# Amplifier_Module_A.net
KiCad netlist of a schematic drawn in EasyEDA Pro
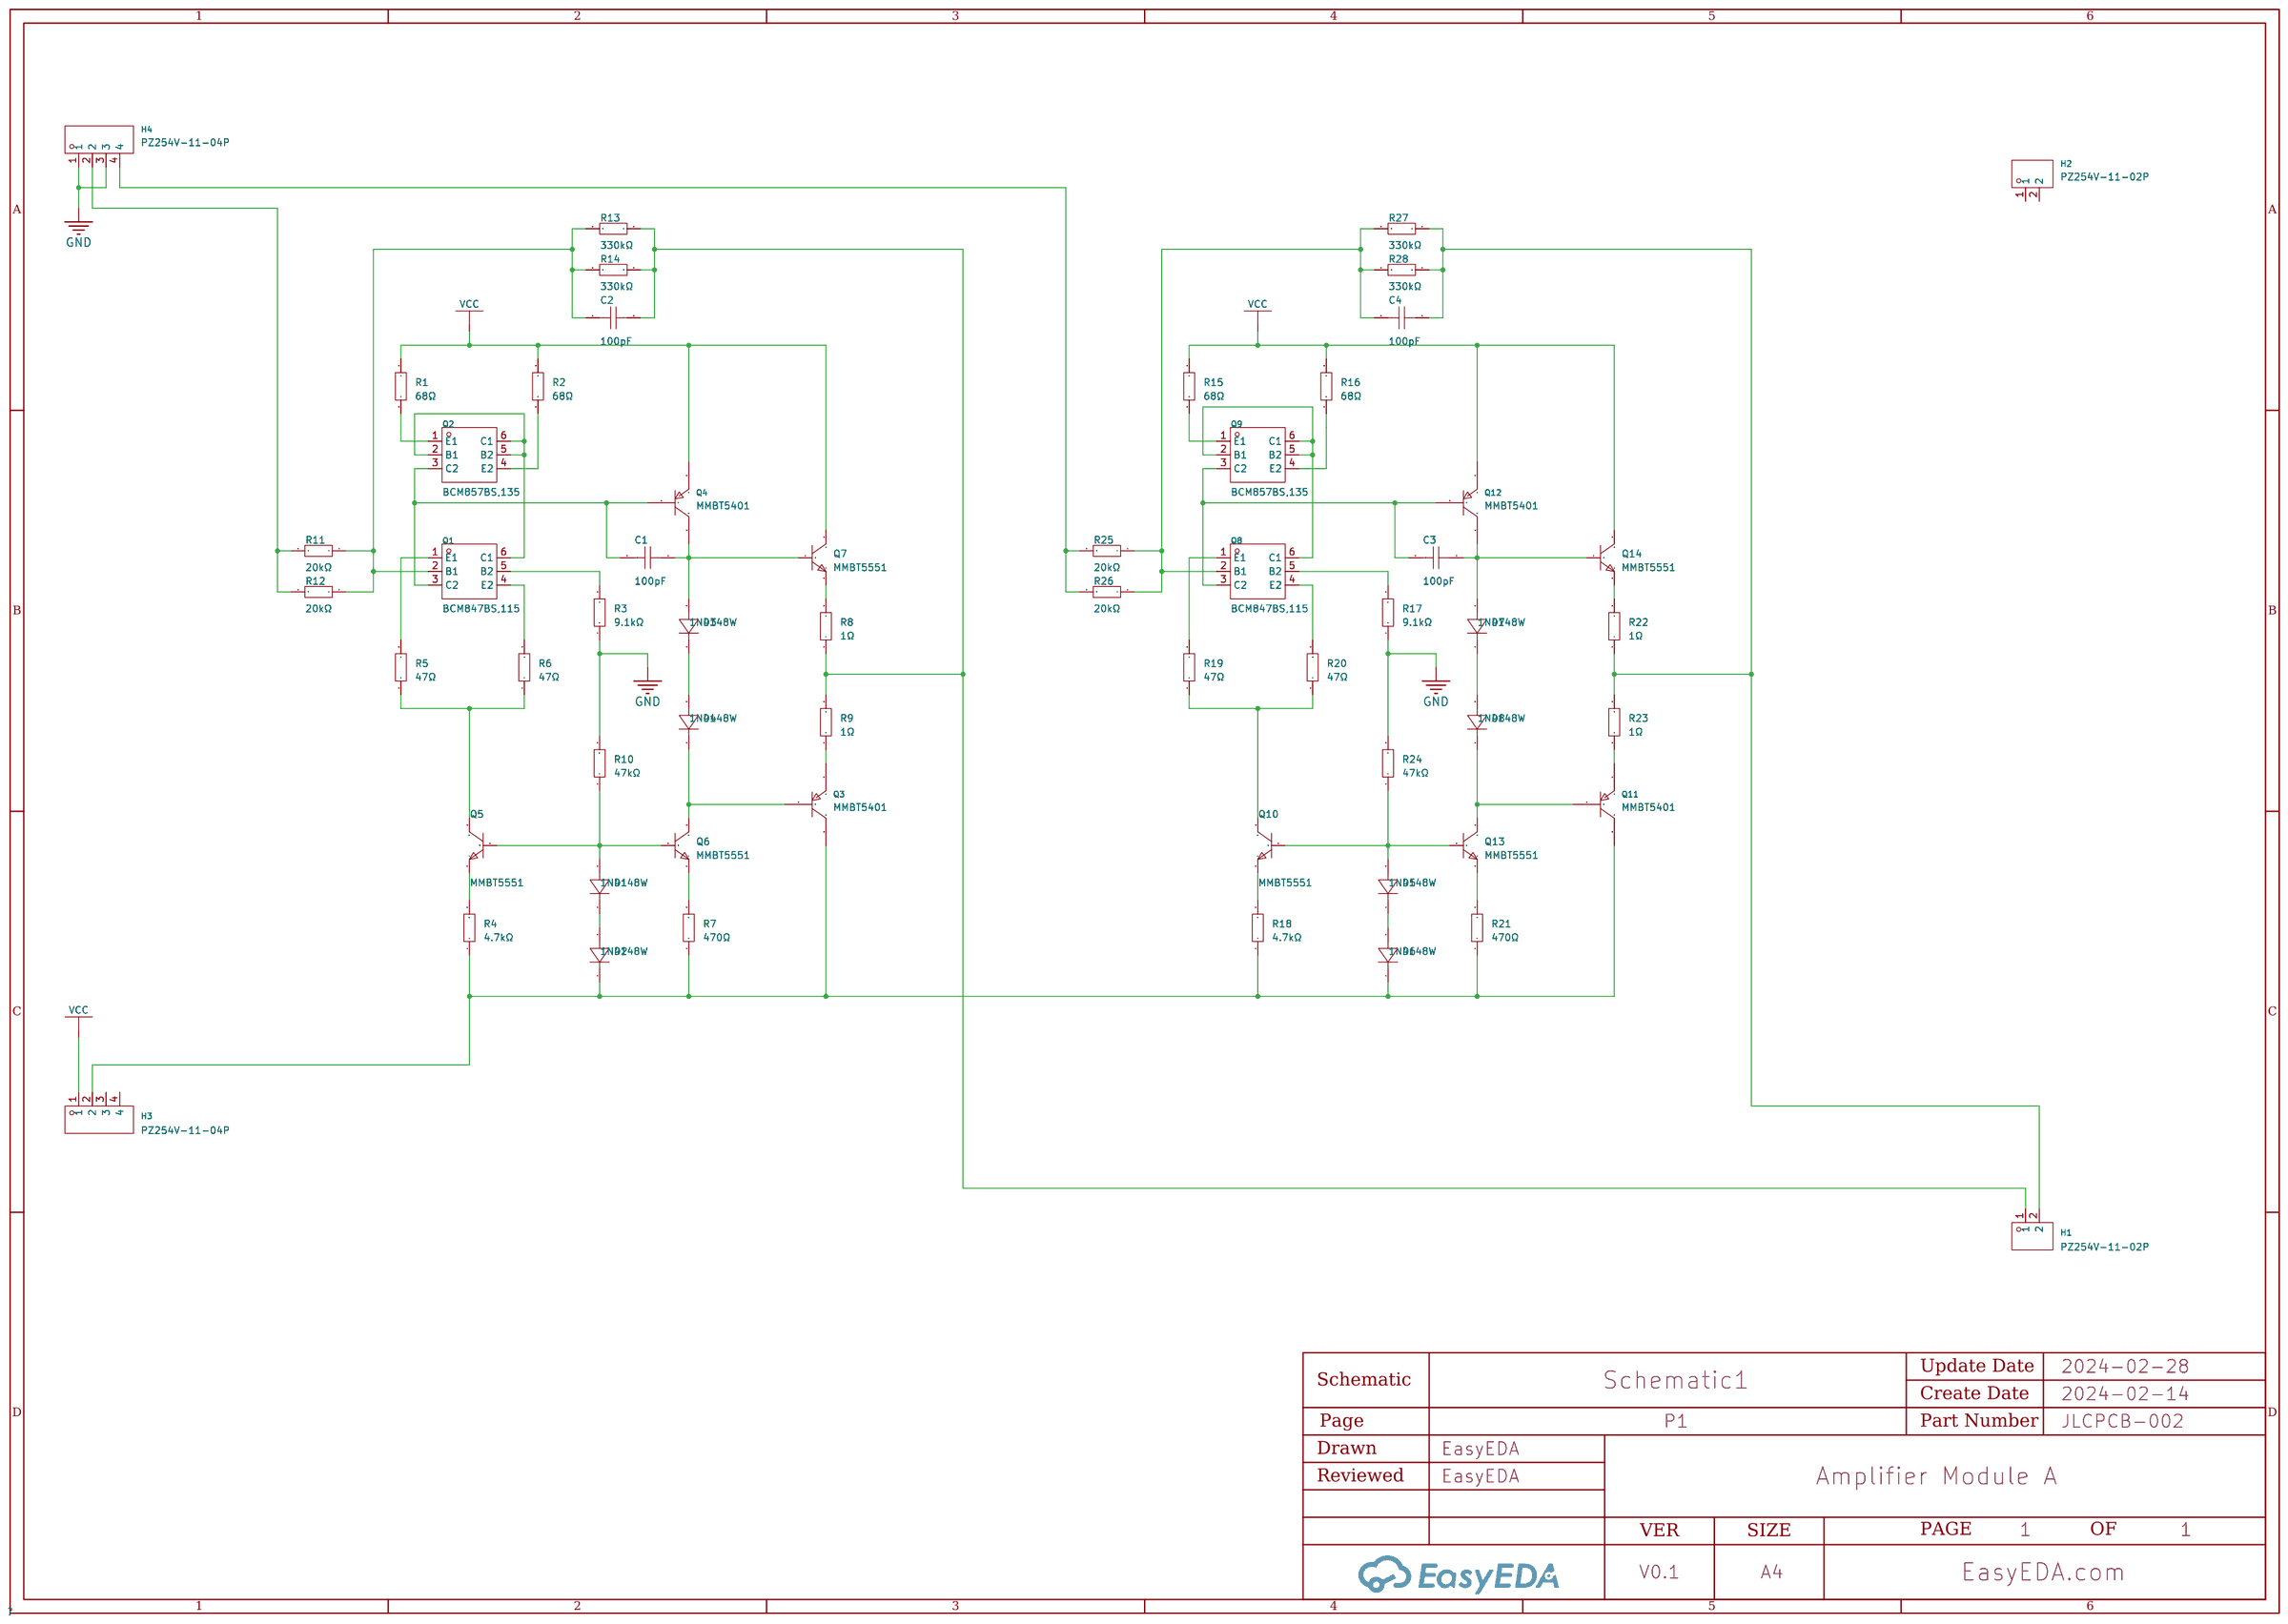
[diagram p0: schematic sheet]

(export (version "E")
  (design (tool "Eeschema 10.0.6"))
  (components
    (comp (ref "C1")
      (value "100pF")
      (footprint "easyedapro:C0603")
      (fields (field (name "Manufacturer Part") "0603CG101J101NT") (field (name "Manufacturer") "FH(风华)"))
      (libsource (lib "easyedapro") (part "CAP"))
    )
    (comp (ref "C2")
      (value "100pF")
      (footprint "easyedapro:C0603")
      (fields (field (name "Manufacturer Part") "0603CG101J101NT") (field (name "Manufacturer") "FH(风华)"))
      (libsource (lib "easyedapro") (part "CAP"))
    )
    (comp (ref "C3")
      (value "100pF")
      (footprint "easyedapro:C0603")
      (fields (field (name "Manufacturer Part") "0603CG101J101NT") (field (name "Manufacturer") "FH(风华)"))
      (libsource (lib "easyedapro") (part "CAP"))
    )
    (comp (ref "C4")
      (value "100pF")
      (footprint "easyedapro:C0603")
      (fields (field (name "Manufacturer Part") "0603CG101J101NT") (field (name "Manufacturer") "FH(风华)"))
      (libsource (lib "easyedapro") (part "CAP"))
    )
    (comp (ref "D1")
      (value "1N4148W")
      (footprint "easyedapro:DO-41_BD2.4-L4.7-P8.70-D0.9-RD")
      (fields (field (name "Manufacturer") "ST(先科)"))
      (libsource (lib "easyedapro") (part "D_1N4007"))
    )
    (comp (ref "D2")
      (value "1N4148W")
      (footprint "easyedapro:DO-41_BD2.4-L4.7-P8.70-D0.9-RD")
      (fields (field (name "Manufacturer") "ST(先科)"))
      (libsource (lib "easyedapro") (part "D_1N4007"))
    )
    (comp (ref "D3")
      (value "1N4148W")
      (footprint "easyedapro:DO-41_BD2.4-L4.7-P8.70-D0.9-RD")
      (fields (field (name "Manufacturer") "ST(先科)"))
      (libsource (lib "easyedapro") (part "D_1N4007"))
    )
    (comp (ref "D4")
      (value "1N4148W")
      (footprint "easyedapro:DO-41_BD2.4-L4.7-P8.70-D0.9-RD")
      (fields (field (name "Manufacturer") "ST(先科)"))
      (libsource (lib "easyedapro") (part "D_1N4007"))
    )
    (comp (ref "D5")
      (value "1N4148W")
      (footprint "easyedapro:DO-41_BD2.4-L4.7-P8.70-D0.9-RD")
      (fields (field (name "Manufacturer") "ST(先科)"))
      (libsource (lib "easyedapro") (part "D_1N4007"))
    )
    (comp (ref "D6")
      (value "1N4148W")
      (footprint "easyedapro:DO-41_BD2.4-L4.7-P8.70-D0.9-RD")
      (fields (field (name "Manufacturer") "ST(先科)"))
      (libsource (lib "easyedapro") (part "D_1N4007"))
    )
    (comp (ref "D7")
      (value "1N4148W")
      (footprint "easyedapro:DO-41_BD2.4-L4.7-P8.70-D0.9-RD")
      (fields (field (name "Manufacturer") "ST(先科)"))
      (libsource (lib "easyedapro") (part "D_1N4007"))
    )
    (comp (ref "D8")
      (value "1N4148W")
      (footprint "easyedapro:DO-41_BD2.4-L4.7-P8.70-D0.9-RD")
      (fields (field (name "Manufacturer") "ST(先科)"))
      (libsource (lib "easyedapro") (part "D_1N4007"))
    )
    (comp (ref "H1")
      (value "PZ254V-11-02P")
      (footprint "easyedapro:HDR-TH_2P-P2.54-V-M")
      (fields (field (name "Manufacturer") "XFCN(兴飞)"))
      (libsource (lib "easyedapro") (part "PZ254V-11-02P"))
    )
    (comp (ref "H2")
      (value "PZ254V-11-02P")
      (footprint "easyedapro:HDR-TH_2P-P2.54-V-M")
      (fields (field (name "Manufacturer") "XFCN(兴飞)"))
      (libsource (lib "easyedapro") (part "PZ254V-11-02P"))
    )
    (comp (ref "H3")
      (value "PZ254V-11-04P")
      (footprint "easyedapro:HDR-TH_4P-P2.54-V-M")
      (fields (field (name "Manufacturer") "XFCN(兴飞)"))
      (libsource (lib "easyedapro") (part "PZ254V-11-04P_C2691448"))
    )
    (comp (ref "H4")
      (value "PZ254V-11-04P")
      (footprint "easyedapro:HDR-TH_4P-P2.54-V-M")
      (fields (field (name "Manufacturer") "XFCN(兴飞)"))
      (libsource (lib "easyedapro") (part "PZ254V-11-04P_C2691448"))
    )
    (comp (ref "Q1")
      (value "BCM847BS,115")
      (footprint "easyedapro:SOT-363_L2.0-W1.3-P0.65-LS2.1-TL")
      (fields (field (name "Manufacturer") "Nexperia(安世)"))
      (libsource (lib "easyedapro") (part "BCM847BS,115"))
    )
    (comp (ref "Q2")
      (value "BCM857BS,135")
      (footprint "easyedapro:SOT-363_L2.0-W1.3-P0.65-LS2.1-BL")
      (fields (field (name "Manufacturer") "Nexperia(安世)"))
      (libsource (lib "easyedapro") (part "BCM857BS,135"))
    )
    (comp (ref "Q3")
      (value "MMBT5401")
      (footprint "easyedapro:SOT-23-3_L2.9-W1.6-P1.90-LS2.8-BR")
      (fields (field (name "Manufacturer") "CJ(江苏长电/长晶)"))
      (libsource (lib "easyedapro") (part "MMBT5401_C83941"))
    )
    (comp (ref "Q4")
      (value "MMBT5401")
      (footprint "easyedapro:SOT-23-3_L2.9-W1.6-P1.90-LS2.8-BR")
      (fields (field (name "Manufacturer") "CJ(江苏长电/长晶)"))
      (libsource (lib "easyedapro") (part "MMBT5401_C83941"))
    )
    (comp (ref "Q5")
      (value "MMBT5551")
      (footprint "easyedapro:SOT-23-3_L2.9-W1.6-P1.90-LS2.8-BR")
      (fields (field (name "Manufacturer") "CJ(江苏长电/长晶)"))
      (libsource (lib "easyedapro") (part "MMBT5551_C7603181"))
    )
    (comp (ref "Q6")
      (value "MMBT5551")
      (footprint "easyedapro:SOT-23-3_L2.9-W1.6-P1.90-LS2.8-BR")
      (fields (field (name "Manufacturer") "CJ(江苏长电/长晶)"))
      (libsource (lib "easyedapro") (part "MMBT5551_C7603181"))
    )
    (comp (ref "Q7")
      (value "MMBT5551")
      (footprint "easyedapro:SOT-23-3_L2.9-W1.6-P1.90-LS2.8-BR")
      (fields (field (name "Manufacturer") "CJ(江苏长电/长晶)"))
      (libsource (lib "easyedapro") (part "MMBT5551_C7603181"))
    )
    (comp (ref "Q8")
      (value "BCM847BS,115")
      (footprint "easyedapro:SOT-363_L2.0-W1.3-P0.65-LS2.1-TL")
      (fields (field (name "Manufacturer") "Nexperia(安世)"))
      (libsource (lib "easyedapro") (part "BCM847BS,115"))
    )
    (comp (ref "Q9")
      (value "BCM857BS,135")
      (footprint "easyedapro:SOT-363_L2.0-W1.3-P0.65-LS2.1-BL")
      (fields (field (name "Manufacturer") "Nexperia(安世)"))
      (libsource (lib "easyedapro") (part "BCM857BS,135"))
    )
    (comp (ref "Q10")
      (value "MMBT5551")
      (footprint "easyedapro:SOT-23-3_L2.9-W1.6-P1.90-LS2.8-BR")
      (fields (field (name "Manufacturer") "CJ(江苏长电/长晶)"))
      (libsource (lib "easyedapro") (part "MMBT5551_C7603181"))
    )
    (comp (ref "Q11")
      (value "MMBT5401")
      (footprint "easyedapro:SOT-23-3_L2.9-W1.6-P1.90-LS2.8-BR")
      (fields (field (name "Manufacturer") "CJ(江苏长电/长晶)"))
      (libsource (lib "easyedapro") (part "MMBT5401_C83941"))
    )
    (comp (ref "Q12")
      (value "MMBT5401")
      (footprint "easyedapro:SOT-23-3_L2.9-W1.6-P1.90-LS2.8-BR")
      (fields (field (name "Manufacturer") "CJ(江苏长电/长晶)"))
      (libsource (lib "easyedapro") (part "MMBT5401_C83941"))
    )
    (comp (ref "Q13")
      (value "MMBT5551")
      (footprint "easyedapro:SOT-23-3_L2.9-W1.6-P1.90-LS2.8-BR")
      (fields (field (name "Manufacturer") "CJ(江苏长电/长晶)"))
      (libsource (lib "easyedapro") (part "MMBT5551_C7603181"))
    )
    (comp (ref "Q14")
      (value "MMBT5551")
      (footprint "easyedapro:SOT-23-3_L2.9-W1.6-P1.90-LS2.8-BR")
      (fields (field (name "Manufacturer") "CJ(江苏长电/长晶)"))
      (libsource (lib "easyedapro") (part "MMBT5551_C7603181"))
    )
    (comp (ref "R1")
      (value "68Ω")
      (footprint "easyedapro:R0603")
      (fields
        (field (name "Manufacturer Part") "0603WAF680JT5E")
        (field (name "Manufacturer") "UNI-ROYAL(厚声)")
      )
      (libsource (lib "easyedapro") (part "Res"))
    )
    (comp (ref "R2")
      (value "68Ω")
      (footprint "easyedapro:R0603")
      (fields
        (field (name "Manufacturer Part") "0603WAF680JT5E")
        (field (name "Manufacturer") "UNI-ROYAL(厚声)")
      )
      (libsource (lib "easyedapro") (part "Res"))
    )
    (comp (ref "R3")
      (value "9.1kΩ")
      (footprint "easyedapro:R0603")
      (fields
        (field (name "Manufacturer Part") "0603WAF9101T5E")
        (field (name "Manufacturer") "UNI-ROYAL(厚声)")
      )
      (libsource (lib "easyedapro") (part "Res"))
    )
    (comp (ref "R4")
      (value "4.7kΩ")
      (footprint "easyedapro:R0603")
      (fields
        (field (name "Manufacturer Part") "0603WAF4701T5E")
        (field (name "Manufacturer") "UNI-ROYAL(厚声)")
      )
      (libsource (lib "easyedapro") (part "Res"))
    )
    (comp (ref "R5")
      (value "47Ω")
      (footprint "easyedapro:R0603")
      (fields
        (field (name "Manufacturer Part") "0603WAF470JT5E")
        (field (name "Manufacturer") "UNI-ROYAL(厚声)")
      )
      (libsource (lib "easyedapro") (part "Res"))
    )
    (comp (ref "R6")
      (value "47Ω")
      (footprint "easyedapro:R0603")
      (fields
        (field (name "Manufacturer Part") "0603WAF470JT5E")
        (field (name "Manufacturer") "UNI-ROYAL(厚声)")
      )
      (libsource (lib "easyedapro") (part "Res"))
    )
    (comp (ref "R7")
      (value "470Ω")
      (footprint "easyedapro:R0603")
      (fields
        (field (name "Manufacturer Part") "0603WAF4700T5E")
        (field (name "Manufacturer") "UNI-ROYAL(厚声)")
      )
      (libsource (lib "easyedapro") (part "Res"))
    )
    (comp (ref "R8")
      (value "1Ω")
      (footprint "easyedapro:R0603")
      (fields
        (field (name "Manufacturer Part") "0603WAF100KT5E")
        (field (name "Manufacturer") "UNI-ROYAL(厚声)")
      )
      (libsource (lib "easyedapro") (part "Res"))
    )
    (comp (ref "R9")
      (value "1Ω")
      (footprint "easyedapro:R0603")
      (fields
        (field (name "Manufacturer Part") "0603WAF100KT5E")
        (field (name "Manufacturer") "UNI-ROYAL(厚声)")
      )
      (libsource (lib "easyedapro") (part "Res"))
    )
    (comp (ref "R10")
      (value "47kΩ")
      (footprint "easyedapro:R0603")
      (fields
        (field (name "Manufacturer Part") "0603WAF4702T5E")
        (field (name "Manufacturer") "UNI-ROYAL(厚声)")
      )
      (libsource (lib "easyedapro") (part "Res"))
    )
    (comp (ref "R11")
      (value "20kΩ")
      (footprint "easyedapro:R0603")
      (fields
        (field (name "Manufacturer Part") "0603WAF2002T5E")
        (field (name "Manufacturer") "UNI-ROYAL(厚声)")
      )
      (libsource (lib "easyedapro") (part "Res"))
    )
    (comp (ref "R12")
      (value "20kΩ")
      (footprint "easyedapro:R0603")
      (fields
        (field (name "Manufacturer Part") "0603WAF2002T5E")
        (field (name "Manufacturer") "UNI-ROYAL(厚声)")
      )
      (libsource (lib "easyedapro") (part "Res"))
    )
    (comp (ref "R13")
      (value "330kΩ")
      (footprint "easyedapro:R0603")
      (fields
        (field (name "Manufacturer Part") "0603WAF3303T5E")
        (field (name "Manufacturer") "UNI-ROYAL(厚声)")
      )
      (libsource (lib "easyedapro") (part "Res"))
    )
    (comp (ref "R14")
      (value "330kΩ")
      (footprint "easyedapro:R0603")
      (fields
        (field (name "Manufacturer Part") "0603WAF3303T5E")
        (field (name "Manufacturer") "UNI-ROYAL(厚声)")
      )
      (libsource (lib "easyedapro") (part "Res"))
    )
    (comp (ref "R15")
      (value "68Ω")
      (footprint "easyedapro:R0603")
      (fields
        (field (name "Manufacturer Part") "0603WAF680JT5E")
        (field (name "Manufacturer") "UNI-ROYAL(厚声)")
      )
      (libsource (lib "easyedapro") (part "Res"))
    )
    (comp (ref "R16")
      (value "68Ω")
      (footprint "easyedapro:R0603")
      (fields
        (field (name "Manufacturer Part") "0603WAF680JT5E")
        (field (name "Manufacturer") "UNI-ROYAL(厚声)")
      )
      (libsource (lib "easyedapro") (part "Res"))
    )
    (comp (ref "R17")
      (value "9.1kΩ")
      (footprint "easyedapro:R0603")
      (fields
        (field (name "Manufacturer Part") "0603WAF9101T5E")
        (field (name "Manufacturer") "UNI-ROYAL(厚声)")
      )
      (libsource (lib "easyedapro") (part "Res"))
    )
    (comp (ref "R18")
      (value "4.7kΩ")
      (footprint "easyedapro:R0603")
      (fields
        (field (name "Manufacturer Part") "0603WAF4701T5E")
        (field (name "Manufacturer") "UNI-ROYAL(厚声)")
      )
      (libsource (lib "easyedapro") (part "Res"))
    )
    (comp (ref "R19")
      (value "47Ω")
      (footprint "easyedapro:R0603")
      (fields
        (field (name "Manufacturer Part") "0603WAF470JT5E")
        (field (name "Manufacturer") "UNI-ROYAL(厚声)")
      )
      (libsource (lib "easyedapro") (part "Res"))
    )
    (comp (ref "R20")
      (value "47Ω")
      (footprint "easyedapro:R0603")
      (fields
        (field (name "Manufacturer Part") "0603WAF470JT5E")
        (field (name "Manufacturer") "UNI-ROYAL(厚声)")
      )
      (libsource (lib "easyedapro") (part "Res"))
    )
    (comp (ref "R21")
      (value "470Ω")
      (footprint "easyedapro:R0603")
      (fields
        (field (name "Manufacturer Part") "0603WAF4700T5E")
        (field (name "Manufacturer") "UNI-ROYAL(厚声)")
      )
      (libsource (lib "easyedapro") (part "Res"))
    )
    (comp (ref "R22")
      (value "1Ω")
      (footprint "easyedapro:R0603")
      (fields
        (field (name "Manufacturer Part") "0603WAF100KT5E")
        (field (name "Manufacturer") "UNI-ROYAL(厚声)")
      )
      (libsource (lib "easyedapro") (part "Res"))
    )
    (comp (ref "R23")
      (value "1Ω")
      (footprint "easyedapro:R0603")
      (fields
        (field (name "Manufacturer Part") "0603WAF100KT5E")
        (field (name "Manufacturer") "UNI-ROYAL(厚声)")
      )
      (libsource (lib "easyedapro") (part "Res"))
    )
    (comp (ref "R24")
      (value "47kΩ")
      (footprint "easyedapro:R0603")
      (fields
        (field (name "Manufacturer Part") "0603WAF4702T5E")
        (field (name "Manufacturer") "UNI-ROYAL(厚声)")
      )
      (libsource (lib "easyedapro") (part "Res"))
    )
    (comp (ref "R25")
      (value "20kΩ")
      (footprint "easyedapro:R0603")
      (fields
        (field (name "Manufacturer Part") "0603WAF2002T5E")
        (field (name "Manufacturer") "UNI-ROYAL(厚声)")
      )
      (libsource (lib "easyedapro") (part "Res"))
    )
    (comp (ref "R26")
      (value "20kΩ")
      (footprint "easyedapro:R0603")
      (fields
        (field (name "Manufacturer Part") "0603WAF2002T5E")
        (field (name "Manufacturer") "UNI-ROYAL(厚声)")
      )
      (libsource (lib "easyedapro") (part "Res"))
    )
    (comp (ref "R27")
      (value "330kΩ")
      (footprint "easyedapro:R0603")
      (fields
        (field (name "Manufacturer Part") "0603WAF3303T5E")
        (field (name "Manufacturer") "UNI-ROYAL(厚声)")
      )
      (libsource (lib "easyedapro") (part "Res"))
    )
    (comp (ref "R28")
      (value "330kΩ")
      (footprint "easyedapro:R0603")
      (fields
        (field (name "Manufacturer Part") "0603WAF3303T5E")
        (field (name "Manufacturer") "UNI-ROYAL(厚声)")
      )
      (libsource (lib "easyedapro") (part "Res"))
    )
  )
  (nets
    (net (code "1") (name "GND") (class "Default")
      (node (ref "H4") (pin "1") (pinfunction "1_1") (pintype "input"))
      (node (ref "H4") (pin "3") (pinfunction "3_3") (pintype "input"))
      (node (ref "R10") (pin "2") (pinfunction "2_2") (pintype "input"))
      (node (ref "R17") (pin "1") (pinfunction "1_1") (pintype "input"))
      (node (ref "R24") (pin "2") (pinfunction "2_2") (pintype "input"))
      (node (ref "R3") (pin "1") (pinfunction "1_1") (pintype "input"))
    )
    (net (code "2") (name "Net-(C2-Pad1)") (class "Default")
      (node (ref "C2") (pin "1") (pinfunction "1_1") (pintype "input"))
      (node (ref "H1") (pin "1") (pinfunction "1_1") (pintype "input"))
      (node (ref "R13") (pin "1") (pinfunction "1_1") (pintype "input"))
      (node (ref "R14") (pin "1") (pinfunction "1_1") (pintype "input"))
      (node (ref "R8") (pin "1") (pinfunction "1_1") (pintype "input"))
      (node (ref "R9") (pin "2") (pinfunction "2_2") (pintype "input"))
    )
    (net (code "3") (name "Net-(C4-Pad1)") (class "Default")
      (node (ref "C4") (pin "1") (pinfunction "1_1") (pintype "input"))
      (node (ref "H1") (pin "2") (pinfunction "2_2") (pintype "input"))
      (node (ref "R22") (pin "1") (pinfunction "1_1") (pintype "input"))
      (node (ref "R23") (pin "2") (pinfunction "2_2") (pintype "input"))
      (node (ref "R27") (pin "1") (pinfunction "1_1") (pintype "input"))
      (node (ref "R28") (pin "1") (pinfunction "1_1") (pintype "input"))
    )
    (net (code "4") (name "Net-(D1-A)") (class "Default")
      (node (ref "D1") (pin "2") (pinfunction "A_2") (pintype "input"))
      (node (ref "Q5") (pin "1") (pinfunction "B_1") (pintype "input"))
      (node (ref "Q6") (pin "1") (pinfunction "B_1") (pintype "input"))
      (node (ref "R10") (pin "1") (pinfunction "1_1") (pintype "input"))
    )
    (net (code "5") (name "Net-(D1-K)") (class "Default")
      (node (ref "D1") (pin "1") (pinfunction "K_1") (pintype "input"))
      (node (ref "D2") (pin "2") (pinfunction "A_2") (pintype "input"))
    )
    (net (code "6") (name "Net-(D2-K)") (class "Default")
      (node (ref "D2") (pin "1") (pinfunction "K_1") (pintype "input"))
      (node (ref "D6") (pin "1") (pinfunction "K_1") (pintype "input"))
      (node (ref "H3") (pin "2") (pinfunction "2_2") (pintype "input"))
      (node (ref "Q11") (pin "3") (pinfunction "C_3") (pintype "input"))
      (node (ref "Q3") (pin "3") (pinfunction "C_3") (pintype "input"))
      (node (ref "R18") (pin "1") (pinfunction "1_1") (pintype "input"))
      (node (ref "R21") (pin "1") (pinfunction "1_1") (pintype "input"))
      (node (ref "R4") (pin "1") (pinfunction "1_1") (pintype "input"))
      (node (ref "R7") (pin "1") (pinfunction "1_1") (pintype "input"))
    )
    (net (code "7") (name "Net-(D3-A)") (class "Default")
      (node (ref "C1") (pin "1") (pinfunction "1_1") (pintype "input"))
      (node (ref "D3") (pin "2") (pinfunction "A_2") (pintype "input"))
      (node (ref "Q4") (pin "3") (pinfunction "C_3") (pintype "input"))
      (node (ref "Q7") (pin "1") (pinfunction "B_1") (pintype "input"))
    )
    (net (code "8") (name "Net-(D3-K)") (class "Default")
      (node (ref "D3") (pin "1") (pinfunction "K_1") (pintype "input"))
      (node (ref "D4") (pin "2") (pinfunction "A_2") (pintype "input"))
    )
    (net (code "9") (name "Net-(D4-K)") (class "Default")
      (node (ref "D4") (pin "1") (pinfunction "K_1") (pintype "input"))
      (node (ref "Q3") (pin "1") (pinfunction "B_1") (pintype "input"))
      (node (ref "Q6") (pin "3") (pinfunction "C_3") (pintype "input"))
    )
    (net (code "10") (name "Net-(D5-A)") (class "Default")
      (node (ref "D5") (pin "2") (pinfunction "A_2") (pintype "input"))
      (node (ref "Q10") (pin "1") (pinfunction "B_1") (pintype "input"))
      (node (ref "Q13") (pin "1") (pinfunction "B_1") (pintype "input"))
      (node (ref "R24") (pin "1") (pinfunction "1_1") (pintype "input"))
    )
    (net (code "11") (name "Net-(D5-K)") (class "Default")
      (node (ref "D5") (pin "1") (pinfunction "K_1") (pintype "input"))
      (node (ref "D6") (pin "2") (pinfunction "A_2") (pintype "input"))
    )
    (net (code "12") (name "Net-(D7-A)") (class "Default")
      (node (ref "C3") (pin "1") (pinfunction "1_1") (pintype "input"))
      (node (ref "D7") (pin "2") (pinfunction "A_2") (pintype "input"))
      (node (ref "Q12") (pin "3") (pinfunction "C_3") (pintype "input"))
      (node (ref "Q14") (pin "1") (pinfunction "B_1") (pintype "input"))
    )
    (net (code "13") (name "Net-(D7-K)") (class "Default")
      (node (ref "D7") (pin "1") (pinfunction "K_1") (pintype "input"))
      (node (ref "D8") (pin "2") (pinfunction "A_2") (pintype "input"))
    )
    (net (code "14") (name "Net-(D8-K)") (class "Default")
      (node (ref "D8") (pin "1") (pinfunction "K_1") (pintype "input"))
      (node (ref "Q11") (pin "1") (pinfunction "B_1") (pintype "input"))
      (node (ref "Q13") (pin "3") (pinfunction "C_3") (pintype "input"))
    )
    (net (code "15") (name "Net-(H4-Pad2)") (class "Default")
      (node (ref "H4") (pin "2") (pinfunction "2_2") (pintype "input"))
      (node (ref "R11") (pin "2") (pinfunction "2_2") (pintype "input"))
      (node (ref "R12") (pin "2") (pinfunction "2_2") (pintype "input"))
    )
    (net (code "16") (name "Net-(H4-Pad4)") (class "Default")
      (node (ref "H4") (pin "4") (pinfunction "4_4") (pintype "input"))
      (node (ref "R25") (pin "2") (pinfunction "2_2") (pintype "input"))
      (node (ref "R26") (pin "2") (pinfunction "2_2") (pintype "input"))
    )
    (net (code "17") (name "Net-(Q1-B1)") (class "Default")
      (node (ref "C2") (pin "2") (pinfunction "2_2") (pintype "input"))
      (node (ref "Q1") (pin "2") (pinfunction "B1_2") (pintype "input"))
      (node (ref "R11") (pin "1") (pinfunction "1_1") (pintype "input"))
      (node (ref "R12") (pin "1") (pinfunction "1_1") (pintype "input"))
      (node (ref "R13") (pin "2") (pinfunction "2_2") (pintype "input"))
      (node (ref "R14") (pin "2") (pinfunction "2_2") (pintype "input"))
    )
    (net (code "18") (name "Net-(Q1-B2)") (class "Default")
      (node (ref "Q1") (pin "5") (pinfunction "B2_5") (pintype "input"))
      (node (ref "R3") (pin "2") (pinfunction "2_2") (pintype "input"))
    )
    (net (code "19") (name "Net-(Q1-C1)") (class "Default")
      (node (ref "Q1") (pin "6") (pinfunction "C1_6") (pintype "input"))
      (node (ref "Q2") (pin "2") (pinfunction "B1_2") (pintype "input"))
      (node (ref "Q2") (pin "5") (pinfunction "B2_5") (pintype "input"))
      (node (ref "Q2") (pin "6") (pinfunction "C1_6") (pintype "input"))
    )
    (net (code "20") (name "Net-(Q1-C2)") (class "Default")
      (node (ref "C1") (pin "2") (pinfunction "2_2") (pintype "input"))
      (node (ref "Q1") (pin "3") (pinfunction "C2_3") (pintype "input"))
      (node (ref "Q2") (pin "3") (pinfunction "C2_3") (pintype "input"))
      (node (ref "Q4") (pin "1") (pinfunction "B_1") (pintype "input"))
    )
    (net (code "21") (name "Net-(Q1-E1)") (class "Default")
      (node (ref "Q1") (pin "1") (pinfunction "E1_1") (pintype "input"))
      (node (ref "R5") (pin "2") (pinfunction "2_2") (pintype "input"))
    )
    (net (code "22") (name "Net-(Q1-E2)") (class "Default")
      (node (ref "Q1") (pin "4") (pinfunction "E2_4") (pintype "input"))
      (node (ref "R6") (pin "2") (pinfunction "2_2") (pintype "input"))
    )
    (net (code "23") (name "Net-(Q2-E1)") (class "Default")
      (node (ref "Q2") (pin "1") (pinfunction "E1_1") (pintype "input"))
      (node (ref "R1") (pin "1") (pinfunction "1_1") (pintype "input"))
    )
    (net (code "24") (name "Net-(Q2-E2)") (class "Default")
      (node (ref "Q2") (pin "4") (pinfunction "E2_4") (pintype "input"))
      (node (ref "R2") (pin "1") (pinfunction "1_1") (pintype "input"))
    )
    (net (code "25") (name "Net-(Q3-E)") (class "Default")
      (node (ref "Q3") (pin "2") (pinfunction "E_2") (pintype "input"))
      (node (ref "R9") (pin "1") (pinfunction "1_1") (pintype "input"))
    )
    (net (code "26") (name "Net-(Q5-C)") (class "Default")
      (node (ref "Q5") (pin "3") (pinfunction "C_3") (pintype "input"))
      (node (ref "R5") (pin "1") (pinfunction "1_1") (pintype "input"))
      (node (ref "R6") (pin "1") (pinfunction "1_1") (pintype "input"))
    )
    (net (code "27") (name "Net-(Q5-E)") (class "Default")
      (node (ref "Q5") (pin "2") (pinfunction "E_2") (pintype "input"))
      (node (ref "R4") (pin "2") (pinfunction "2_2") (pintype "input"))
    )
    (net (code "28") (name "Net-(Q6-E)") (class "Default")
      (node (ref "Q6") (pin "2") (pinfunction "E_2") (pintype "input"))
      (node (ref "R7") (pin "2") (pinfunction "2_2") (pintype "input"))
    )
    (net (code "29") (name "Net-(Q7-E)") (class "Default")
      (node (ref "Q7") (pin "2") (pinfunction "E_2") (pintype "input"))
      (node (ref "R8") (pin "2") (pinfunction "2_2") (pintype "input"))
    )
    (net (code "30") (name "Net-(Q8-B1)") (class "Default")
      (node (ref "C4") (pin "2") (pinfunction "2_2") (pintype "input"))
      (node (ref "Q8") (pin "2") (pinfunction "B1_2") (pintype "input"))
      (node (ref "R25") (pin "1") (pinfunction "1_1") (pintype "input"))
      (node (ref "R26") (pin "1") (pinfunction "1_1") (pintype "input"))
      (node (ref "R27") (pin "2") (pinfunction "2_2") (pintype "input"))
      (node (ref "R28") (pin "2") (pinfunction "2_2") (pintype "input"))
    )
    (net (code "31") (name "Net-(Q8-B2)") (class "Default")
      (node (ref "Q8") (pin "5") (pinfunction "B2_5") (pintype "input"))
      (node (ref "R17") (pin "2") (pinfunction "2_2") (pintype "input"))
    )
    (net (code "32") (name "Net-(Q8-C1)") (class "Default")
      (node (ref "Q8") (pin "6") (pinfunction "C1_6") (pintype "input"))
      (node (ref "Q9") (pin "2") (pinfunction "B1_2") (pintype "input"))
      (node (ref "Q9") (pin "5") (pinfunction "B2_5") (pintype "input"))
      (node (ref "Q9") (pin "6") (pinfunction "C1_6") (pintype "input"))
    )
    (net (code "33") (name "Net-(Q8-E1)") (class "Default")
      (node (ref "Q8") (pin "1") (pinfunction "E1_1") (pintype "input"))
      (node (ref "R19") (pin "2") (pinfunction "2_2") (pintype "input"))
    )
    (net (code "34") (name "Net-(Q8-E2)") (class "Default")
      (node (ref "Q8") (pin "4") (pinfunction "E2_4") (pintype "input"))
      (node (ref "R20") (pin "2") (pinfunction "2_2") (pintype "input"))
    )
    (net (code "35") (name "Net-(Q9-E1)") (class "Default")
      (node (ref "Q9") (pin "1") (pinfunction "E1_1") (pintype "input"))
      (node (ref "R15") (pin "1") (pinfunction "1_1") (pintype "input"))
    )
    (net (code "36") (name "Net-(Q9-E2)") (class "Default")
      (node (ref "Q9") (pin "4") (pinfunction "E2_4") (pintype "input"))
      (node (ref "R16") (pin "1") (pinfunction "1_1") (pintype "input"))
    )
    (net (code "37") (name "Net-(Q10-C)") (class "Default")
      (node (ref "Q10") (pin "3") (pinfunction "C_3") (pintype "input"))
      (node (ref "R19") (pin "1") (pinfunction "1_1") (pintype "input"))
      (node (ref "R20") (pin "1") (pinfunction "1_1") (pintype "input"))
    )
    (net (code "38") (name "Net-(Q10-E)") (class "Default")
      (node (ref "Q10") (pin "2") (pinfunction "E_2") (pintype "input"))
      (node (ref "R18") (pin "2") (pinfunction "2_2") (pintype "input"))
    )
    (net (code "39") (name "Net-(Q11-E)") (class "Default")
      (node (ref "Q11") (pin "2") (pinfunction "E_2") (pintype "input"))
      (node (ref "R23") (pin "1") (pinfunction "1_1") (pintype "input"))
    )
    (net (code "40") (name "Net-(Q12-B)") (class "Default")
      (node (ref "C3") (pin "2") (pinfunction "2_2") (pintype "input"))
      (node (ref "Q12") (pin "1") (pinfunction "B_1") (pintype "input"))
      (node (ref "Q8") (pin "3") (pinfunction "C2_3") (pintype "input"))
      (node (ref "Q9") (pin "3") (pinfunction "C2_3") (pintype "input"))
    )
    (net (code "41") (name "Net-(Q13-E)") (class "Default")
      (node (ref "Q13") (pin "2") (pinfunction "E_2") (pintype "input"))
      (node (ref "R21") (pin "2") (pinfunction "2_2") (pintype "input"))
    )
    (net (code "42") (name "Net-(Q14-E)") (class "Default")
      (node (ref "Q14") (pin "2") (pinfunction "E_2") (pintype "input"))
      (node (ref "R22") (pin "2") (pinfunction "2_2") (pintype "input"))
    )
    (net (code "43") (name "VCC") (class "Default")
      (node (ref "H3") (pin "1") (pinfunction "1_1") (pintype "input"))
      (node (ref "Q12") (pin "2") (pinfunction "E_2") (pintype "input"))
      (node (ref "Q14") (pin "3") (pinfunction "C_3") (pintype "input"))
      (node (ref "Q4") (pin "2") (pinfunction "E_2") (pintype "input"))
      (node (ref "Q7") (pin "3") (pinfunction "C_3") (pintype "input"))
      (node (ref "R1") (pin "2") (pinfunction "2_2") (pintype "input"))
      (node (ref "R15") (pin "2") (pinfunction "2_2") (pintype "input"))
      (node (ref "R16") (pin "2") (pinfunction "2_2") (pintype "input"))
      (node (ref "R2") (pin "2") (pinfunction "2_2") (pintype "input"))
    )
    (net (code "44") (name "unconnected-(H2-Pad1)") (class "Default")
      (node (ref "H2") (pin "1") (pinfunction "1_1") (pintype "input"))
    )
    (net (code "45") (name "unconnected-(H2-Pad2)") (class "Default")
      (node (ref "H2") (pin "2") (pinfunction "2_2") (pintype "input"))
    )
    (net (code "46") (name "unconnected-(H3-Pad3)") (class "Default")
      (node (ref "H3") (pin "3") (pinfunction "3_3") (pintype "input"))
    )
    (net (code "47") (name "unconnected-(H3-Pad4)") (class "Default")
      (node (ref "H3") (pin "4") (pinfunction "4_4") (pintype "input"))
    )
  )
)
